# MiniPowerAdaptor.net
KiCad netlist of a schematic drawn in EAGLE
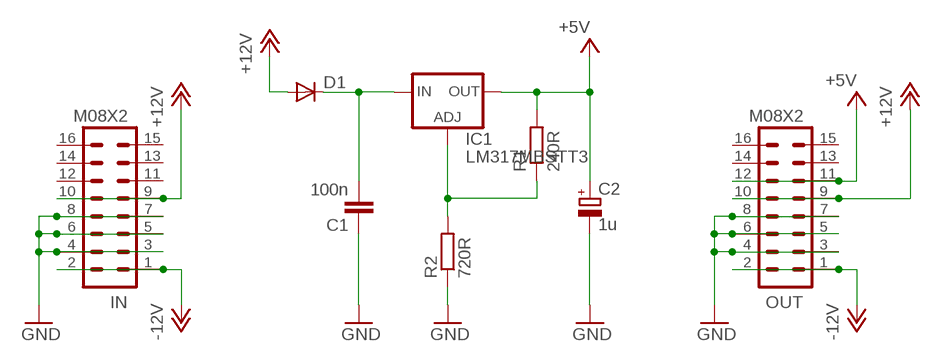
[diagram p0: schematic, sheet 1]

(export (version "E")
  (design (tool "Eeschema 10.0.6"))
  (components
    (comp (ref "C1")
      (value "100n")
      (footprint "eagle-import:C0603")
      (libsource (lib "eagle-import") (part "C-EUC0603"))
    )
    (comp (ref "C2")
      (value "1u")
      (footprint "eagle-import:SANYO-OSCON_SMD_A5")
      (libsource (lib "eagle-import") (part "CPOL-EUSANYO_SMD_A5"))
    )
    (comp (ref "D1")
      (value "DIODESMA")
      (footprint "eagle-import:SMA-DIODE")
      (libsource (lib "eagle-import") (part "DIODESMA"))
    )
    (comp (ref "IC1")
      (value "LM317MBSTT3")
      (footprint "eagle-import:SOT223")
      (libsource (lib "eagle-import") (part "LM317?MBSTT3"))
    )
    (comp (ref "IN")
      (value "M08X2")
      (footprint "eagle-import:2X8")
      (libsource (lib "eagle-import") (part "M08X2"))
    )
    (comp (ref "OUT")
      (value "M08X2")
      (footprint "eagle-import:2X8")
      (libsource (lib "eagle-import") (part "M08X2"))
    )
    (comp (ref "R1")
      (value "240R")
      (footprint "eagle-import:0603")
      (libsource (lib "eagle-import") (part "R-EU_0603"))
    )
    (comp (ref "R2")
      (value "720R")
      (footprint "eagle-import:0603")
      (libsource (lib "eagle-import") (part "R-EU_0603"))
    )
  )
  (nets
    (net (code "1") (name "+5V") (class "Default")
      (node (ref "C2") (pin "+") (pinfunction "+_+") (pintype "passive"))
      (node (ref "IC1") (pin "4") (pinfunction "OUT_4") (pintype "passive"))
      (node (ref "OUT") (pin "11") (pinfunction "11_11") (pintype "passive"))
      (node (ref "OUT") (pin "12") (pinfunction "12_12") (pintype "passive"))
      (node (ref "R1") (pin "2") (pinfunction "2_2") (pintype "passive"))
    )
    (net (code "2") (name "+12V") (class "Default")
      (node (ref "D1") (pin "A") (pinfunction "A_A") (pintype "passive"))
      (node (ref "IN") (pin "10") (pinfunction "10_10") (pintype "passive"))
      (node (ref "IN") (pin "9") (pinfunction "9_9") (pintype "passive"))
      (node (ref "OUT") (pin "10") (pinfunction "10_10") (pintype "passive"))
      (node (ref "OUT") (pin "9") (pinfunction "9_9") (pintype "passive"))
    )
    (net (code "3") (name "-12V") (class "Default")
      (node (ref "IN") (pin "1") (pinfunction "1_1") (pintype "passive"))
      (node (ref "IN") (pin "2") (pinfunction "2_2") (pintype "passive"))
      (node (ref "OUT") (pin "1") (pinfunction "1_1") (pintype "passive"))
      (node (ref "OUT") (pin "2") (pinfunction "2_2") (pintype "passive"))
    )
    (net (code "4") (name "GND") (class "Default")
      (node (ref "C1") (pin "1") (pinfunction "1_1") (pintype "passive"))
      (node (ref "C2") (pin "-") (pinfunction "-_-") (pintype "passive"))
      (node (ref "IN") (pin "3") (pinfunction "3_3") (pintype "passive"))
      (node (ref "IN") (pin "4") (pinfunction "4_4") (pintype "passive"))
      (node (ref "IN") (pin "5") (pinfunction "5_5") (pintype "passive"))
      (node (ref "IN") (pin "6") (pinfunction "6_6") (pintype "passive"))
      (node (ref "IN") (pin "7") (pinfunction "7_7") (pintype "passive"))
      (node (ref "IN") (pin "8") (pinfunction "8_8") (pintype "passive"))
      (node (ref "OUT") (pin "3") (pinfunction "3_3") (pintype "passive"))
      (node (ref "OUT") (pin "4") (pinfunction "4_4") (pintype "passive"))
      (node (ref "OUT") (pin "5") (pinfunction "5_5") (pintype "passive"))
      (node (ref "OUT") (pin "6") (pinfunction "6_6") (pintype "passive"))
      (node (ref "OUT") (pin "7") (pinfunction "7_7") (pintype "passive"))
      (node (ref "OUT") (pin "8") (pinfunction "8_8") (pintype "passive"))
      (node (ref "R2") (pin "1") (pinfunction "1_1") (pintype "passive"))
    )
    (net (code "5") (name "Net-(IC1-ADJ)") (class "Default")
      (node (ref "IC1") (pin "1") (pinfunction "ADJ_1") (pintype "input"))
      (node (ref "R1") (pin "1") (pinfunction "1_1") (pintype "passive"))
      (node (ref "R2") (pin "2") (pinfunction "2_2") (pintype "passive"))
    )
    (net (code "6") (name "Net-(IC1-IN)") (class "Default")
      (node (ref "C1") (pin "2") (pinfunction "2_2") (pintype "passive"))
      (node (ref "D1") (pin "C") (pinfunction "C_C") (pintype "passive"))
      (node (ref "IC1") (pin "3") (pinfunction "IN_3") (pintype "input"))
    )
    (net (code "7") (name "unconnected-(IN-Pad11)") (class "Default")
      (node (ref "IN") (pin "11") (pinfunction "11_11") (pintype "passive"))
    )
    (net (code "8") (name "unconnected-(IN-Pad12)") (class "Default")
      (node (ref "IN") (pin "12") (pinfunction "12_12") (pintype "passive"))
    )
    (net (code "9") (name "unconnected-(IN-Pad13)") (class "Default")
      (node (ref "IN") (pin "13") (pinfunction "13_13") (pintype "passive"))
    )
    (net (code "10") (name "unconnected-(IN-Pad14)") (class "Default")
      (node (ref "IN") (pin "14") (pinfunction "14_14") (pintype "passive"))
    )
    (net (code "11") (name "unconnected-(IN-Pad15)") (class "Default")
      (node (ref "IN") (pin "15") (pinfunction "15_15") (pintype "passive"))
    )
    (net (code "12") (name "unconnected-(IN-Pad16)") (class "Default")
      (node (ref "IN") (pin "16") (pinfunction "16_16") (pintype "passive"))
    )
    (net (code "13") (name "unconnected-(OUT-Pad13)") (class "Default")
      (node (ref "OUT") (pin "13") (pinfunction "13_13") (pintype "passive"))
    )
    (net (code "14") (name "unconnected-(OUT-Pad14)") (class "Default")
      (node (ref "OUT") (pin "14") (pinfunction "14_14") (pintype "passive"))
    )
    (net (code "15") (name "unconnected-(OUT-Pad15)") (class "Default")
      (node (ref "OUT") (pin "15") (pinfunction "15_15") (pintype "passive"))
    )
    (net (code "16") (name "unconnected-(OUT-Pad16)") (class "Default")
      (node (ref "OUT") (pin "16") (pinfunction "16_16") (pintype "passive"))
    )
  )
)
